# CAN_Hub.net
KiCad netlist of a schematic drawn in Altium Designer
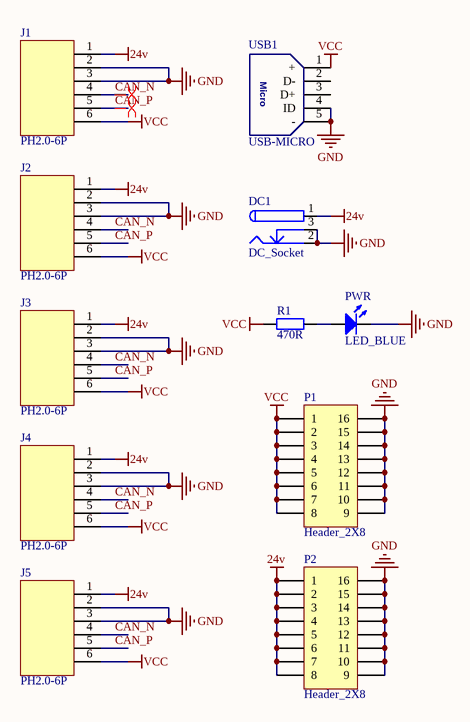
[diagram p0: CAN_Hub.SchDoc]

(export (version "E")
  (design (tool "Eeschema 10.0.6"))
  (components
    (comp (ref "DC1")
      (value "DC_Socket")
      (footprint "DC-005")
      (description "DC电源座")
      (libsource (lib "Miscellaneous Socket") (part "DC_Socket"))
    )
    (comp (ref "J1") (value "PH2.0-6P") (footprint "PH2.0-6P") (libsource (lib "PH") (part "PH2.0-6P")))
    (comp (ref "J2") (value "PH2.0-6P") (footprint "PH2.0-6P") (libsource (lib "PH") (part "PH2.0-6P")))
    (comp (ref "J3") (value "PH2.0-6P") (footprint "PH2.0-6P") (libsource (lib "PH") (part "PH2.0-6P")))
    (comp (ref "J4") (value "PH2.0-6P") (footprint "PH2.0-6P") (libsource (lib "PH") (part "PH2.0-6P")))
    (comp (ref "J5") (value "PH2.0-6P") (footprint "PH2.0-6P") (libsource (lib "PH") (part "PH2.0-6P")))
    (comp (ref "P1")
      (value "Header_2X8")
      (footprint "Header_SMD_2.54X8")
      (libsource (lib "Miscellaneous Header") (part "Header_2X8"))
    )
    (comp (ref "P2")
      (value "Header_2X8")
      (footprint "Header_SMD_2.54X8")
      (libsource (lib "Miscellaneous Header") (part "Header_2X8"))
    )
    (comp (ref "PWR")
      (value "LED_BLUE")
      (footprint "LED_0603_B")
      (description "发光二极管")
      (libsource (lib "Miscellaneous Transistor") (part "LED_SMD_BLUE"))
    )
    (comp (ref "R1")
      (value "470R")
      (footprint "Res-0603")
      (description "贴片电阻")
      (libsource (lib "Miscellaneous Base") (part "RES"))
    )
    (comp (ref "USB1")
      (value "USB-MICRO")
      (footprint "USB-MICRO-SMD_C")
      (libsource (lib "Miscellaneous Socket") (part "USB-MICRO"))
    )
  )
  (nets
    (net (code "1") (name "/CAN_N") (class "Default")
      (node (ref "J1") (pin "4") (pinfunction "4_4") (pintype "passive"))
      (node (ref "J2") (pin "4") (pinfunction "4_4") (pintype "passive"))
      (node (ref "J3") (pin "4") (pinfunction "4_4") (pintype "passive"))
      (node (ref "J4") (pin "4") (pinfunction "4_4") (pintype "passive"))
      (node (ref "J5") (pin "4") (pinfunction "4_4") (pintype "passive"))
    )
    (net (code "2") (name "/CAN_P") (class "Default")
      (node (ref "J1") (pin "5") (pinfunction "5_5") (pintype "passive"))
      (node (ref "J2") (pin "5") (pinfunction "5_5") (pintype "passive"))
      (node (ref "J3") (pin "5") (pinfunction "5_5") (pintype "passive"))
      (node (ref "J4") (pin "5") (pinfunction "5_5") (pintype "passive"))
      (node (ref "J5") (pin "5") (pinfunction "5_5") (pintype "passive"))
    )
    (net (code "3") (name "24v") (class "Default")
      (node (ref "DC1") (pin "1") (pinfunction "1_1") (pintype "power_in"))
      (node (ref "J1") (pin "1") (pinfunction "1_1") (pintype "passive"))
      (node (ref "J2") (pin "1") (pinfunction "1_1") (pintype "passive"))
      (node (ref "J3") (pin "1") (pinfunction "1_1") (pintype "passive"))
      (node (ref "J4") (pin "1") (pinfunction "1_1") (pintype "passive"))
      (node (ref "J5") (pin "1") (pinfunction "1_1") (pintype "passive"))
      (node (ref "P2") (pin "1") (pinfunction "1_1") (pintype "power_in"))
      (node (ref "P2") (pin "2") (pinfunction "2_2") (pintype "power_in"))
      (node (ref "P2") (pin "3") (pinfunction "3_3") (pintype "power_in"))
      (node (ref "P2") (pin "4") (pinfunction "4_4") (pintype "power_in"))
      (node (ref "P2") (pin "5") (pinfunction "5_5") (pintype "power_in"))
      (node (ref "P2") (pin "6") (pinfunction "6_6") (pintype "power_in"))
      (node (ref "P2") (pin "7") (pinfunction "7_7") (pintype "power_in"))
      (node (ref "P2") (pin "8") (pinfunction "8_8") (pintype "power_in"))
    )
    (net (code "4") (name "GND") (class "Default")
      (node (ref "DC1") (pin "2") (pinfunction "2_2") (pintype "power_in"))
      (node (ref "DC1") (pin "3") (pinfunction "3_3") (pintype "power_in"))
      (node (ref "J1") (pin "2") (pinfunction "2_2") (pintype "passive"))
      (node (ref "J1") (pin "3") (pinfunction "3_3") (pintype "passive"))
      (node (ref "J2") (pin "2") (pinfunction "2_2") (pintype "passive"))
      (node (ref "J2") (pin "3") (pinfunction "3_3") (pintype "passive"))
      (node (ref "J3") (pin "2") (pinfunction "2_2") (pintype "passive"))
      (node (ref "J3") (pin "3") (pinfunction "3_3") (pintype "passive"))
      (node (ref "J4") (pin "2") (pinfunction "2_2") (pintype "passive"))
      (node (ref "J4") (pin "3") (pinfunction "3_3") (pintype "passive"))
      (node (ref "J5") (pin "2") (pinfunction "2_2") (pintype "passive"))
      (node (ref "J5") (pin "3") (pinfunction "3_3") (pintype "passive"))
      (node (ref "P1") (pin "10") (pinfunction "10_10") (pintype "power_in"))
      (node (ref "P1") (pin "11") (pinfunction "11_11") (pintype "power_in"))
      (node (ref "P1") (pin "12") (pinfunction "12_12") (pintype "power_in"))
      (node (ref "P1") (pin "13") (pinfunction "13_13") (pintype "power_in"))
      (node (ref "P1") (pin "14") (pinfunction "14_14") (pintype "power_in"))
      (node (ref "P1") (pin "15") (pinfunction "15_15") (pintype "power_in"))
      (node (ref "P1") (pin "16") (pinfunction "16_16") (pintype "power_in"))
      (node (ref "P1") (pin "9") (pinfunction "9_9") (pintype "power_in"))
      (node (ref "P2") (pin "10") (pinfunction "10_10") (pintype "power_in"))
      (node (ref "P2") (pin "11") (pinfunction "11_11") (pintype "power_in"))
      (node (ref "P2") (pin "12") (pinfunction "12_12") (pintype "power_in"))
      (node (ref "P2") (pin "13") (pinfunction "13_13") (pintype "power_in"))
      (node (ref "P2") (pin "14") (pinfunction "14_14") (pintype "power_in"))
      (node (ref "P2") (pin "15") (pinfunction "15_15") (pintype "power_in"))
      (node (ref "P2") (pin "16") (pinfunction "16_16") (pintype "power_in"))
      (node (ref "P2") (pin "9") (pinfunction "9_9") (pintype "power_in"))
      (node (ref "PWR") (pin "2") (pinfunction "K_2") (pintype "passive"))
      (node (ref "USB1") (pin "4") (pinfunction "ID_4") (pintype "passive"))
      (node (ref "USB1") (pin "5") (pinfunction "-_5") (pintype "passive"))
    )
    (net (code "5") (name "Net-(PWR-A)") (class "Default")
      (node (ref "PWR") (pin "1") (pinfunction "A_1") (pintype "passive"))
      (node (ref "R1") (pin "2") (pinfunction "2_2") (pintype "passive"))
    )
    (net (code "6") (name "VCC") (class "Default")
      (node (ref "J1") (pin "6") (pinfunction "6_6") (pintype "passive"))
      (node (ref "J2") (pin "6") (pinfunction "6_6") (pintype "passive"))
      (node (ref "J3") (pin "6") (pinfunction "6_6") (pintype "passive"))
      (node (ref "J4") (pin "6") (pinfunction "6_6") (pintype "passive"))
      (node (ref "J5") (pin "6") (pinfunction "6_6") (pintype "passive"))
      (node (ref "P1") (pin "1") (pinfunction "1_1") (pintype "power_in"))
      (node (ref "P1") (pin "2") (pinfunction "2_2") (pintype "power_in"))
      (node (ref "P1") (pin "3") (pinfunction "3_3") (pintype "power_in"))
      (node (ref "P1") (pin "4") (pinfunction "4_4") (pintype "power_in"))
      (node (ref "P1") (pin "5") (pinfunction "5_5") (pintype "power_in"))
      (node (ref "P1") (pin "6") (pinfunction "6_6") (pintype "power_in"))
      (node (ref "P1") (pin "7") (pinfunction "7_7") (pintype "power_in"))
      (node (ref "P1") (pin "8") (pinfunction "8_8") (pintype "power_in"))
      (node (ref "R1") (pin "1") (pinfunction "1_1") (pintype "passive"))
      (node (ref "USB1") (pin "1") (pinfunction "+_1") (pintype "passive"))
    )
    (net (code "7") (name "unconnected-(USB1-D+-Pad3)") (class "Default")
      (node (ref "USB1") (pin "3") (pinfunction "D+_3") (pintype "passive"))
    )
    (net (code "8") (name "unconnected-(USB1-D--Pad2)") (class "Default")
      (node (ref "USB1") (pin "2") (pinfunction "D-_2") (pintype "passive"))
    )
  )
)
